# Grabber_DIOT.net
KiCad netlist of a schematic drawn in Altium Designer
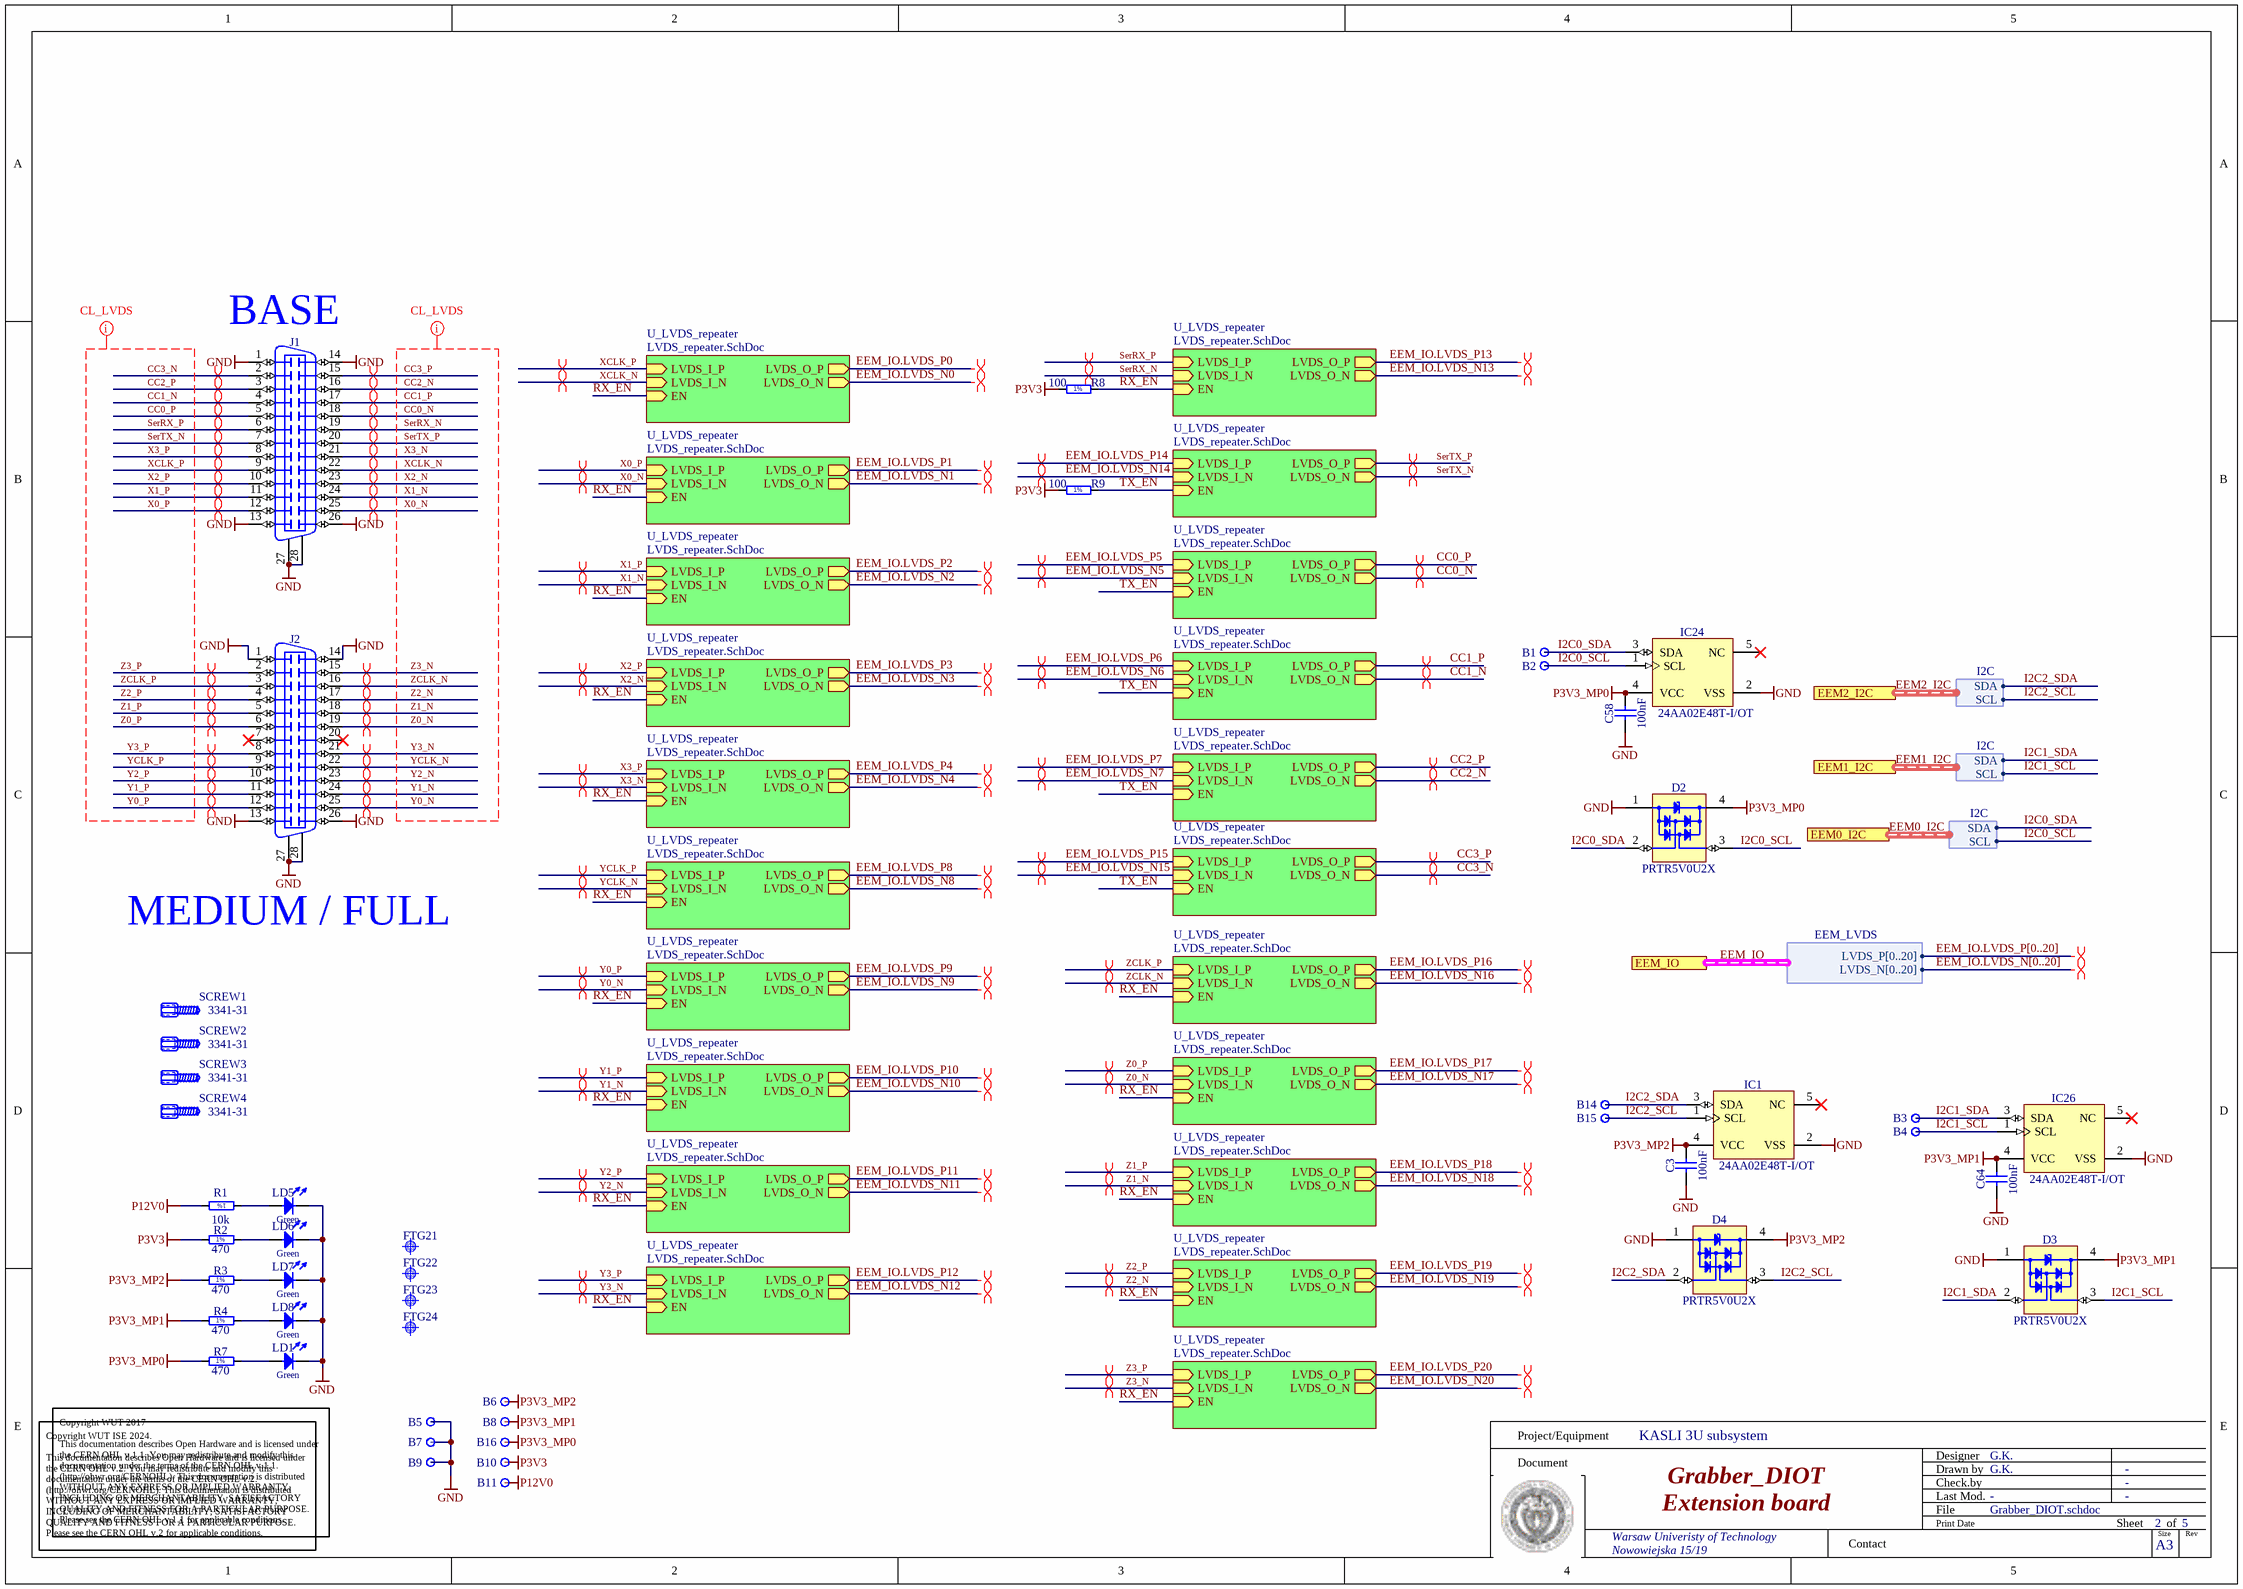
[diagram p0: Grabber_DIOT.schdoc]

(export (version "E")
  (design (tool "Eeschema 10.0.6"))
  (components
    (comp (ref "B1")
      (value "Plated Hole")
      (footprint "c100h50")
      (description "Single Terminal Socket")
      (fields (field (name "PART NUMBER") "PLATED_HOLE0.6_PAD1.3") (field (name "AUTHOR") "CERN DEM MR"))
      (libsource (lib "Eletro-mechanical") (part "Single Terminal Socket"))
    )
    (comp (ref "B2")
      (value "Plated Hole")
      (footprint "c100h50")
      (description "Single Terminal Socket")
      (fields (field (name "PART NUMBER") "PLATED_HOLE0.6_PAD1.3") (field (name "AUTHOR") "CERN DEM MR"))
      (libsource (lib "Eletro-mechanical") (part "Single Terminal Socket"))
    )
    (comp (ref "B3")
      (value "Plated Hole")
      (footprint "c100h50")
      (description "Single Terminal Socket")
      (fields (field (name "PART NUMBER") "PLATED_HOLE0.6_PAD1.3") (field (name "AUTHOR") "CERN DEM MR"))
      (libsource (lib "Eletro-mechanical") (part "Single Terminal Socket"))
    )
    (comp (ref "B4")
      (value "Plated Hole")
      (footprint "c100h50")
      (description "Single Terminal Socket")
      (fields (field (name "PART NUMBER") "PLATED_HOLE0.6_PAD1.3") (field (name "AUTHOR") "CERN DEM MR"))
      (libsource (lib "Eletro-mechanical") (part "Single Terminal Socket"))
    )
    (comp (ref "B5")
      (value "Plated Hole")
      (footprint "c100h50")
      (description "Single Terminal Socket")
      (fields (field (name "PART NUMBER") "PLATED_HOLE0.6_PAD1.3") (field (name "AUTHOR") "CERN DEM MR"))
      (libsource (lib "Eletro-mechanical") (part "Single Terminal Socket"))
    )
    (comp (ref "B6")
      (value "Plated Hole")
      (footprint "c100h50")
      (description "Single Terminal Socket")
      (fields (field (name "PART NUMBER") "PLATED_HOLE0.6_PAD1.3") (field (name "AUTHOR") "CERN DEM MR"))
      (libsource (lib "Eletro-mechanical") (part "Single Terminal Socket"))
    )
    (comp (ref "B7")
      (value "Plated Hole")
      (footprint "c100h50")
      (description "Single Terminal Socket")
      (fields (field (name "PART NUMBER") "PLATED_HOLE0.6_PAD1.3") (field (name "AUTHOR") "CERN DEM MR"))
      (libsource (lib "Eletro-mechanical") (part "Single Terminal Socket"))
    )
    (comp (ref "B8")
      (value "Plated Hole")
      (footprint "c100h50")
      (description "Single Terminal Socket")
      (fields (field (name "PART NUMBER") "PLATED_HOLE0.6_PAD1.3") (field (name "AUTHOR") "CERN DEM MR"))
      (libsource (lib "Eletro-mechanical") (part "Single Terminal Socket"))
    )
    (comp (ref "B9")
      (value "Plated Hole")
      (footprint "c100h50")
      (description "Single Terminal Socket")
      (fields (field (name "PART NUMBER") "PLATED_HOLE0.6_PAD1.3") (field (name "AUTHOR") "CERN DEM MR"))
      (libsource (lib "Eletro-mechanical") (part "Single Terminal Socket"))
    )
    (comp (ref "B10")
      (value "Plated Hole")
      (footprint "c100h50")
      (description "Single Terminal Socket")
      (fields (field (name "PART NUMBER") "PLATED_HOLE0.6_PAD1.3") (field (name "AUTHOR") "CERN DEM MR"))
      (libsource (lib "Eletro-mechanical") (part "Single Terminal Socket"))
    )
    (comp (ref "B11")
      (value "Plated Hole")
      (footprint "c100h50")
      (description "Single Terminal Socket")
      (fields (field (name "PART NUMBER") "PLATED_HOLE0.6_PAD1.3") (field (name "AUTHOR") "CERN DEM MR"))
      (libsource (lib "Eletro-mechanical") (part "Single Terminal Socket"))
    )
    (comp (ref "B14")
      (value "Plated Hole")
      (footprint "c100h50")
      (description "Single Terminal Socket")
      (fields (field (name "PART NUMBER") "PLATED_HOLE0.6_PAD1.3") (field (name "AUTHOR") "CERN DEM MR"))
      (libsource (lib "Eletro-mechanical") (part "Single Terminal Socket"))
    )
    (comp (ref "B15")
      (value "Plated Hole")
      (footprint "c100h50")
      (description "Single Terminal Socket")
      (fields (field (name "PART NUMBER") "PLATED_HOLE0.6_PAD1.3") (field (name "AUTHOR") "CERN DEM MR"))
      (libsource (lib "Eletro-mechanical") (part "Single Terminal Socket"))
    )
    (comp (ref "B16")
      (value "Plated Hole")
      (footprint "c100h50")
      (description "Single Terminal Socket")
      (fields (field (name "PART NUMBER") "PLATED_HOLE0.6_PAD1.3") (field (name "AUTHOR") "CERN DEM MR"))
      (libsource (lib "Eletro-mechanical") (part "Single Terminal Socket"))
    )
    (comp (ref "C3")
      (value "100nF")
      (footprint "CAPC1005X55N")
      (description "Non-polarised capacitor")
      (fields
        (field (name "PART NUMBER") "CC0402_100NF_16V_10%_X5R")
        (field (name "VOLTAGE") "16V")
        (field (name "AUTHOR") "CERN DEM JLC")
      )
      (libsource (lib "Capacitors") (part "Capacitor - non polarized"))
    )
    (comp (ref "C58")
      (value "100nF")
      (footprint "CAPC1005X55N")
      (description "Non-polarised capacitor")
      (fields
        (field (name "PART NUMBER") "CC0402_100NF_16V_10%_X5R")
        (field (name "VOLTAGE") "16V")
        (field (name "AUTHOR") "CERN DEM JLC")
      )
      (libsource (lib "Capacitors") (part "Capacitor - non polarized"))
    )
    (comp (ref "C64")
      (value "100nF")
      (footprint "CAPC1005X55N")
      (description "Non-polarised capacitor")
      (fields
        (field (name "PART NUMBER") "CC0402_100NF_16V_10%_X5R")
        (field (name "VOLTAGE") "16V")
        (field (name "AUTHOR") "CERN DEM JLC")
      )
      (libsource (lib "Capacitors") (part "Capacitor - non polarized"))
    )
    (comp (ref "D2")
      (value "PRTR5V0U2X")
      (footprint "SOT190P230X110-4N")
      (description "Ultra Low Capacitance Double Rail-to-Rail ESD Protection Diode")
      (fields
        (field (name "VOLTAGE") "5.5V")
        (field (name "MANUFACTURER") "NXP SEMICONDUCTORS")
        (field (name "AUTHOR") "CERN DEM JLC")
      )
      (libsource (lib "ICs And Semiconductors") (part "PRTR5V0U2X"))
    )
    (comp (ref "D3")
      (value "PRTR5V0U2X")
      (footprint "SOT190P230X110-4N")
      (description "Ultra Low Capacitance Double Rail-to-Rail ESD Protection Diode")
      (fields
        (field (name "VOLTAGE") "5.5V")
        (field (name "MANUFACTURER") "NXP SEMICONDUCTORS")
        (field (name "AUTHOR") "CERN DEM JLC")
      )
      (libsource (lib "ICs And Semiconductors") (part "PRTR5V0U2X"))
    )
    (comp (ref "D4")
      (value "PRTR5V0U2X")
      (footprint "SOT190P230X110-4N")
      (description "Ultra Low Capacitance Double Rail-to-Rail ESD Protection Diode")
      (fields
        (field (name "VOLTAGE") "5.5V")
        (field (name "MANUFACTURER") "NXP SEMICONDUCTORS")
        (field (name "AUTHOR") "CERN DEM JLC")
      )
      (libsource (lib "ICs And Semiconductors") (part "PRTR5V0U2X"))
    )
    (comp (ref "FTG21")
      (value "Use only in PCB")
      (footprint "FIDUCIAL_TOP_C100-200")
      (description "Fiducial Target")
      (fields (field (name "PART NUMBER") "FIDUCIAL_TARGET_C100-200") (field (name "AUTHOR") "CERN DEM JLC"))
      (libsource (lib "Eletro-mechanical") (part "Fiducial Target"))
    )
    (comp (ref "FTG22")
      (value "Use only in PCB")
      (footprint "FIDUCIAL_TOP_S100-200")
      (description "Fiducial Target")
      (fields (field (name "PART NUMBER") "FIDUCIAL_TARGET_S100-200") (field (name "AUTHOR") "CERN DEM JLC"))
      (libsource (lib "Eletro-mechanical") (part "Fiducial Target"))
    )
    (comp (ref "FTG23")
      (value "Use only in PCB")
      (footprint "FIDUCIAL_TOP_S200-400")
      (description "Fiducial Target")
      (fields (field (name "PART NUMBER") "FIDUCIAL_TARGET_S200-400") (field (name "AUTHOR") "CERN DEM JLC"))
      (libsource (lib "Eletro-mechanical") (part "Fiducial Target"))
    )
    (comp (ref "FTG24")
      (value "Use only in PCB")
      (footprint "FIDUCIAL_TOP_S100-200")
      (description "Fiducial Target")
      (fields (field (name "PART NUMBER") "FIDUCIAL_TARGET_S100-200") (field (name "AUTHOR") "CERN DEM JLC"))
      (libsource (lib "Eletro-mechanical") (part "Fiducial Target"))
    )
    (comp (ref "IC1")
      (value "24AA02E48T-I/OT")
      (footprint "SOT95P280X145-5N")
      (description "1.7V-5.5V, 2K I2C Serial EEPROM With EUI-48 Node Identity")
      (fields (field (name "MANUFACTURER") "MICROCHIP TECHNOLOGY") (field (name "AUTHOR") "CERN DEM MR"))
      (libsource (lib "ICs And Semiconductors") (part "24AA02E48T-I/OT"))
    )
    (comp (ref "IC24")
      (value "24AA02E48T-I/OT")
      (footprint "SOT95P280X145-5N")
      (description "1.7V-5.5V, 2K I2C Serial EEPROM With EUI-48 Node Identity")
      (fields (field (name "MANUFACTURER") "MICROCHIP TECHNOLOGY") (field (name "AUTHOR") "CERN DEM MR"))
      (libsource (lib "ICs And Semiconductors") (part "24AA02E48T-I/OT"))
    )
    (comp (ref "IC26")
      (value "24AA02E48T-I/OT")
      (footprint "SOT95P280X145-5N")
      (description "1.7V-5.5V, 2K I2C Serial EEPROM With EUI-48 Node Identity")
      (fields (field (name "MANUFACTURER") "MICROCHIP TECHNOLOGY") (field (name "AUTHOR") "CERN DEM MR"))
      (libsource (lib "ICs And Semiconductors") (part "24AA02E48T-I/OT"))
    )
    (comp (ref "J1")
      (value "N10226-5212PC")
      (footprint "3M_N10226-5212PC")
      (description "Connector Mini D Ribbon (MDR) 26 Female")
      (fields (field (name "MANUFACTURER") "3M") (field (name "AUTHOR") "CERN DEM JLC"))
      (libsource (lib "Connectors") (part "Connector MDR 26 Female"))
    )
    (comp (ref "J2")
      (value "N10226-5212PC")
      (footprint "3M_N10226-5212PC")
      (description "Connector Mini D Ribbon (MDR) 26 Female")
      (fields (field (name "MANUFACTURER") "3M") (field (name "AUTHOR") "CERN DEM JLC"))
      (libsource (lib "Connectors") (part "Connector MDR 26 Female"))
    )
    (comp (ref "LD1")
      (value "Green")
      (footprint "LED_KINGBRIGHT_KP-1608CGCK")
      (description "LED Green 1C 2A")
      (fields
        (field (name "PART NUMBER") "KPH-1608CGCK")
        (field (name "MANUFACTURER") "KINGBRIGHT")
        (field (name "AUTHOR") "CERN DEM JLC")
      )
      (libsource (lib "ICs And Semiconductors") (part "LED Green 1C 2A"))
    )
    (comp (ref "LD5")
      (value "Green")
      (footprint "LED_KINGBRIGHT_KP-1608CGCK")
      (description "LED Green 1C 2A")
      (fields
        (field (name "PART NUMBER") "KPH-1608CGCK")
        (field (name "MANUFACTURER") "KINGBRIGHT")
        (field (name "AUTHOR") "CERN DEM JLC")
      )
      (libsource (lib "ICs And Semiconductors") (part "LED Green 1C 2A"))
    )
    (comp (ref "LD6")
      (value "Green")
      (footprint "LED_KINGBRIGHT_KP-1608CGCK")
      (description "LED Green 1C 2A")
      (fields
        (field (name "PART NUMBER") "KPH-1608CGCK")
        (field (name "MANUFACTURER") "KINGBRIGHT")
        (field (name "AUTHOR") "CERN DEM JLC")
      )
      (libsource (lib "ICs And Semiconductors") (part "LED Green 1C 2A"))
    )
    (comp (ref "LD7")
      (value "Green")
      (footprint "LED_KINGBRIGHT_KP-1608CGCK")
      (description "LED Green 1C 2A")
      (fields
        (field (name "PART NUMBER") "KPH-1608CGCK")
        (field (name "MANUFACTURER") "KINGBRIGHT")
        (field (name "AUTHOR") "CERN DEM JLC")
      )
      (libsource (lib "ICs And Semiconductors") (part "LED Green 1C 2A"))
    )
    (comp (ref "LD8")
      (value "Green")
      (footprint "LED_KINGBRIGHT_KP-1608CGCK")
      (description "LED Green 1C 2A")
      (fields
        (field (name "PART NUMBER") "KPH-1608CGCK")
        (field (name "MANUFACTURER") "KINGBRIGHT")
        (field (name "AUTHOR") "CERN DEM JLC")
      )
      (libsource (lib "ICs And Semiconductors") (part "LED Green 1C 2A"))
    )
    (comp (ref "R1")
      (value "10k")
      (footprint "RESC1005X40N")
      (description "Resistor - 1%")
      (fields
        (field (name "PART NUMBER") "R0402_10K_1%_0.0625W_100PPM")
        (field (name "POWER") "0.0625W")
        (field (name "AUTHOR") "CERN DEM JLC")
      )
      (libsource (lib "Resistors") (part "Resistor - 1%"))
    )
    (comp (ref "R2")
      (value "470")
      (footprint "RESC1005X40N")
      (description "Resistor - 1%")
      (fields
        (field (name "PART NUMBER") "R0402_470R_1%_0.0625W_100PPM")
        (field (name "POWER") "0.0625W")
        (field (name "AUTHOR") "CERN DEM JLC")
      )
      (libsource (lib "Resistors") (part "Resistor - 1%"))
    )
    (comp (ref "R3")
      (value "470")
      (footprint "RESC1005X40N")
      (description "Resistor - 1%")
      (fields
        (field (name "PART NUMBER") "R0402_470R_1%_0.0625W_100PPM")
        (field (name "POWER") "0.0625W")
        (field (name "AUTHOR") "CERN DEM JLC")
      )
      (libsource (lib "Resistors") (part "Resistor - 1%"))
    )
    (comp (ref "R4")
      (value "470")
      (footprint "RESC1005X40N")
      (description "Resistor - 1%")
      (fields
        (field (name "PART NUMBER") "R0402_470R_1%_0.0625W_100PPM")
        (field (name "POWER") "0.0625W")
        (field (name "AUTHOR") "CERN DEM JLC")
      )
      (libsource (lib "Resistors") (part "Resistor - 1%"))
    )
    (comp (ref "R7")
      (value "470")
      (footprint "RESC1005X40N")
      (description "Resistor - 1%")
      (fields
        (field (name "PART NUMBER") "R0402_470R_1%_0.0625W_100PPM")
        (field (name "POWER") "0.0625W")
        (field (name "AUTHOR") "CERN DEM JLC")
      )
      (libsource (lib "Resistors") (part "Resistor - 1%"))
    )
    (comp (ref "R8")
      (value "100")
      (footprint "RESC1005X40N")
      (description "Resistor - 1%")
      (fields
        (field (name "PART NUMBER") "R0402_100R_1%_0.1W_100PPM")
        (field (name "POWER") "0.1W")
        (field (name "AUTHOR") "CERN DEM JLC")
      )
      (libsource (lib "Resistors") (part "Resistor - 1%"))
    )
    (comp (ref "R9")
      (value "100")
      (footprint "RESC1005X40N")
      (description "Resistor - 1%")
      (fields
        (field (name "PART NUMBER") "R0402_100R_1%_0.1W_100PPM")
        (field (name "POWER") "0.1W")
        (field (name "AUTHOR") "CERN DEM JLC")
      )
      (libsource (lib "Resistors") (part "Resistor - 1%"))
    )
    (comp (ref "SCREW1")
      (value "3341-31")
      (footprint "3M_3341-31")
      (description "VHDCI Female Screw Lock")
      (fields (field (name "MANUFACTURER") "3M") (field (name "AUTHOR") "GK"))
      (libsource (lib "LIBRARY_SCH") (part "MECH_MDR_screw_lock"))
    )
    (comp (ref "SCREW2")
      (value "3341-31")
      (footprint "3M_3341-31")
      (description "VHDCI Female Screw Lock")
      (fields (field (name "MANUFACTURER") "3M") (field (name "AUTHOR") "GK"))
      (libsource (lib "LIBRARY_SCH") (part "MECH_MDR_screw_lock"))
    )
    (comp (ref "SCREW3")
      (value "3341-31")
      (footprint "3M_3341-31")
      (description "VHDCI Female Screw Lock")
      (fields (field (name "MANUFACTURER") "3M") (field (name "AUTHOR") "GK"))
      (libsource (lib "LIBRARY_SCH") (part "MECH_MDR_screw_lock"))
    )
    (comp (ref "SCREW4")
      (value "3341-31")
      (footprint "3M_3341-31")
      (description "VHDCI Female Screw Lock")
      (fields (field (name "MANUFACTURER") "3M") (field (name "AUTHOR") "GK"))
      (libsource (lib "LIBRARY_SCH") (part "MECH_MDR_screw_lock"))
    )
  )
  (nets
    (net (code "5") (name "/CC0_N") (class "Default")
      (node (ref "J1") (pin "18") (pinfunction "18_18") (pintype "bidirectional"))
    )
    (net (code "6") (name "/CC0_P") (class "Default")
      (node (ref "J1") (pin "5") (pinfunction "5_5") (pintype "bidirectional"))
    )
    (net (code "7") (name "/CC1_N") (class "Default")
      (node (ref "J1") (pin "4") (pinfunction "4_4") (pintype "bidirectional"))
    )
    (net (code "8") (name "/CC1_P") (class "Default")
      (node (ref "J1") (pin "17") (pinfunction "17_17") (pintype "bidirectional"))
    )
    (net (code "9") (name "/CC2_N") (class "Default")
      (node (ref "J1") (pin "16") (pinfunction "16_16") (pintype "bidirectional"))
    )
    (net (code "10") (name "/CC2_P") (class "Default")
      (node (ref "J1") (pin "3") (pinfunction "3_3") (pintype "bidirectional"))
    )
    (net (code "11") (name "/CC3_N") (class "Default")
      (node (ref "J1") (pin "2") (pinfunction "2_2") (pintype "bidirectional"))
    )
    (net (code "12") (name "/CC3_P") (class "Default")
      (node (ref "J1") (pin "15") (pinfunction "15_15") (pintype "bidirectional"))
    )
    (net (code "59") (name "/I2C0_SCL") (class "Default")
      (node (ref "B2") (pin "1") (pinfunction "1_1") (pintype "bidirectional"))
      (node (ref "D2") (pin "3") (pinfunction "I/O2_3") (pintype "bidirectional"))
      (node (ref "IC24") (pin "1") (pinfunction "SCL_1") (pintype "input"))
    )
    (net (code "60") (name "/I2C0_SDA") (class "Default")
      (node (ref "B1") (pin "1") (pinfunction "1_1") (pintype "bidirectional"))
      (node (ref "D2") (pin "2") (pinfunction "I/O1_2") (pintype "bidirectional"))
      (node (ref "IC24") (pin "3") (pinfunction "SDA_3") (pintype "bidirectional"))
    )
    (net (code "61") (name "/I2C1_SCL") (class "Default")
      (node (ref "B4") (pin "1") (pinfunction "1_1") (pintype "bidirectional"))
      (node (ref "D3") (pin "3") (pinfunction "I/O2_3") (pintype "bidirectional"))
      (node (ref "IC26") (pin "1") (pinfunction "SCL_1") (pintype "input"))
    )
    (net (code "62") (name "/I2C1_SDA") (class "Default")
      (node (ref "B3") (pin "1") (pinfunction "1_1") (pintype "bidirectional"))
      (node (ref "D3") (pin "2") (pinfunction "I/O1_2") (pintype "bidirectional"))
      (node (ref "IC26") (pin "3") (pinfunction "SDA_3") (pintype "bidirectional"))
    )
    (net (code "63") (name "/I2C2_SCL") (class "Default")
      (node (ref "B15") (pin "1") (pinfunction "1_1") (pintype "bidirectional"))
      (node (ref "D4") (pin "3") (pinfunction "I/O2_3") (pintype "bidirectional"))
      (node (ref "IC1") (pin "1") (pinfunction "SCL_1") (pintype "input"))
    )
    (net (code "64") (name "/I2C2_SDA") (class "Default")
      (node (ref "B14") (pin "1") (pinfunction "1_1") (pintype "bidirectional"))
      (node (ref "D4") (pin "2") (pinfunction "I/O1_2") (pintype "bidirectional"))
      (node (ref "IC1") (pin "3") (pinfunction "SDA_3") (pintype "bidirectional"))
    )
    (net (code "65") (name "/RX_EN") (class "Default")
      (node (ref "R8") (pin "2") (pinfunction "2_2") (pintype "passive"))
    )
    (net (code "66") (name "/SerRX_N") (class "Default")
      (node (ref "J1") (pin "19") (pinfunction "19_19") (pintype "bidirectional"))
    )
    (net (code "67") (name "/SerRX_P") (class "Default")
      (node (ref "J1") (pin "6") (pinfunction "6_6") (pintype "bidirectional"))
    )
    (net (code "68") (name "/SerTX_N") (class "Default")
      (node (ref "J1") (pin "7") (pinfunction "7_7") (pintype "bidirectional"))
    )
    (net (code "69") (name "/SerTX_P") (class "Default")
      (node (ref "J1") (pin "20") (pinfunction "20_20") (pintype "bidirectional"))
    )
    (net (code "70") (name "/TX_EN") (class "Default")
      (node (ref "R9") (pin "2") (pinfunction "2_2") (pintype "passive"))
    )
    (net (code "71") (name "/X0_N") (class "Default")
      (node (ref "J1") (pin "25") (pinfunction "25_25") (pintype "bidirectional"))
    )
    (net (code "72") (name "/X0_P") (class "Default")
      (node (ref "J1") (pin "12") (pinfunction "12_12") (pintype "bidirectional"))
    )
    (net (code "73") (name "/X1_N") (class "Default")
      (node (ref "J1") (pin "24") (pinfunction "24_24") (pintype "bidirectional"))
    )
    (net (code "74") (name "/X1_P") (class "Default")
      (node (ref "J1") (pin "11") (pinfunction "11_11") (pintype "bidirectional"))
    )
    (net (code "75") (name "/X2_N") (class "Default")
      (node (ref "J1") (pin "23") (pinfunction "23_23") (pintype "bidirectional"))
    )
    (net (code "76") (name "/X2_P") (class "Default")
      (node (ref "J1") (pin "10") (pinfunction "10_10") (pintype "bidirectional"))
    )
    (net (code "77") (name "/X3_N") (class "Default")
      (node (ref "J1") (pin "21") (pinfunction "21_21") (pintype "bidirectional"))
    )
    (net (code "78") (name "/X3_P") (class "Default")
      (node (ref "J1") (pin "8") (pinfunction "8_8") (pintype "bidirectional"))
    )
    (net (code "79") (name "/XCLK_N") (class "Default")
      (node (ref "J1") (pin "22") (pinfunction "22_22") (pintype "bidirectional"))
    )
    (net (code "80") (name "/XCLK_P") (class "Default")
      (node (ref "J1") (pin "9") (pinfunction "9_9") (pintype "bidirectional"))
    )
    (net (code "81") (name "/Y0_N") (class "Default")
      (node (ref "J2") (pin "25") (pinfunction "25_25") (pintype "bidirectional"))
    )
    (net (code "82") (name "/Y0_P") (class "Default")
      (node (ref "J2") (pin "12") (pinfunction "12_12") (pintype "bidirectional"))
    )
    (net (code "83") (name "/Y1_N") (class "Default")
      (node (ref "J2") (pin "24") (pinfunction "24_24") (pintype "bidirectional"))
    )
    (net (code "84") (name "/Y1_P") (class "Default")
      (node (ref "J2") (pin "11") (pinfunction "11_11") (pintype "bidirectional"))
    )
    (net (code "85") (name "/Y2_N") (class "Default")
      (node (ref "J2") (pin "23") (pinfunction "23_23") (pintype "bidirectional"))
    )
    (net (code "86") (name "/Y2_P") (class "Default")
      (node (ref "J2") (pin "10") (pinfunction "10_10") (pintype "bidirectional"))
    )
    (net (code "87") (name "/Y3_N") (class "Default")
      (node (ref "J2") (pin "21") (pinfunction "21_21") (pintype "bidirectional"))
    )
    (net (code "88") (name "/Y3_P") (class "Default")
      (node (ref "J2") (pin "8") (pinfunction "8_8") (pintype "bidirectional"))
    )
    (net (code "89") (name "/YCLK_N") (class "Default")
      (node (ref "J2") (pin "22") (pinfunction "22_22") (pintype "bidirectional"))
    )
    (net (code "90") (name "/YCLK_P") (class "Default")
      (node (ref "J2") (pin "9") (pinfunction "9_9") (pintype "bidirectional"))
    )
    (net (code "91") (name "/Z0_N") (class "Default")
      (node (ref "J2") (pin "19") (pinfunction "19_19") (pintype "bidirectional"))
    )
    (net (code "92") (name "/Z0_P") (class "Default")
      (node (ref "J2") (pin "6") (pinfunction "6_6") (pintype "bidirectional"))
    )
    (net (code "93") (name "/Z1_N") (class "Default")
      (node (ref "J2") (pin "18") (pinfunction "18_18") (pintype "bidirectional"))
    )
    (net (code "94") (name "/Z1_P") (class "Default")
      (node (ref "J2") (pin "5") (pinfunction "5_5") (pintype "bidirectional"))
    )
    (net (code "95") (name "/Z2_N") (class "Default")
      (node (ref "J2") (pin "17") (pinfunction "17_17") (pintype "bidirectional"))
    )
    (net (code "96") (name "/Z2_P") (class "Default")
      (node (ref "J2") (pin "4") (pinfunction "4_4") (pintype "bidirectional"))
    )
    (net (code "97") (name "/Z3_N") (class "Default")
      (node (ref "J2") (pin "15") (pinfunction "15_15") (pintype "bidirectional"))
    )
    (net (code "98") (name "/Z3_P") (class "Default")
      (node (ref "J2") (pin "2") (pinfunction "2_2") (pintype "bidirectional"))
    )
    (net (code "99") (name "/ZCLK_N") (class "Default")
      (node (ref "J2") (pin "16") (pinfunction "16_16") (pintype "bidirectional"))
    )
    (net (code "100") (name "/ZCLK_P") (class "Default")
      (node (ref "J2") (pin "3") (pinfunction "3_3") (pintype "bidirectional"))
    )
    (net (code "102") (name "GND") (class "Default")
      (node (ref "B5") (pin "1") (pinfunction "1_1") (pintype "bidirectional"))
      (node (ref "B7") (pin "1") (pinfunction "1_1") (pintype "bidirectional"))
      (node (ref "B9") (pin "1") (pinfunction "1_1") (pintype "bidirectional"))
      (node (ref "C3") (pin "1") (pinfunction "1_1") (pintype "passive"))
      (node (ref "C58") (pin "1") (pinfunction "1_1") (pintype "passive"))
      (node (ref "C64") (pin "1") (pinfunction "1_1") (pintype "passive"))
      (node (ref "D2") (pin "1") (pinfunction "GND_1") (pintype "power_in"))
      (node (ref "D3") (pin "1") (pinfunction "GND_1") (pintype "power_in"))
      (node (ref "D4") (pin "1") (pinfunction "GND_1") (pintype "power_in"))
      (node (ref "IC1") (pin "2") (pinfunction "VSS_2") (pintype "power_in"))
      (node (ref "IC24") (pin "2") (pinfunction "VSS_2") (pintype "power_in"))
      (node (ref "IC26") (pin "2") (pinfunction "VSS_2") (pintype "power_in"))
      (node (ref "J1") (pin "1") (pinfunction "1_1") (pintype "bidirectional"))
      (node (ref "J1") (pin "13") (pinfunction "13_13") (pintype "bidirectional"))
      (node (ref "J1") (pin "14") (pinfunction "14_14") (pintype "bidirectional"))
      (node (ref "J1") (pin "26") (pinfunction "26_26") (pintype "bidirectional"))
      (node (ref "J1") (pin "27") (pinfunction "27_27") (pintype "passive"))
      (node (ref "J1") (pin "28") (pinfunction "28_28") (pintype "passive"))
      (node (ref "J2") (pin "1") (pinfunction "1_1") (pintype "bidirectional"))
      (node (ref "J2") (pin "13") (pinfunction "13_13") (pintype "bidirectional"))
      (node (ref "J2") (pin "14") (pinfunction "14_14") (pintype "bidirectional"))
      (node (ref "J2") (pin "26") (pinfunction "26_26") (pintype "bidirectional"))
      (node (ref "J2") (pin "27") (pinfunction "27_27") (pintype "passive"))
      (node (ref "J2") (pin "28") (pinfunction "28_28") (pintype "passive"))
      (node (ref "LD1") (pin "1") (pinfunction "C_1") (pintype "passive"))
      (node (ref "LD5") (pin "1") (pinfunction "C_1") (pintype "passive"))
      (node (ref "LD6") (pin "1") (pinfunction "C_1") (pintype "passive"))
      (node (ref "LD7") (pin "1") (pinfunction "C_1") (pintype "passive"))
      (node (ref "LD8") (pin "1") (pinfunction "C_1") (pintype "passive"))
    )
    (net (code "103") (name "Net-(LD1-A)") (class "Default")
      (node (ref "LD1") (pin "2") (pinfunction "A_2") (pintype "passive"))
      (node (ref "R7") (pin "2") (pinfunction "2_2") (pintype "passive"))
    )
    (net (code "104") (name "Net-(LD5-A)") (class "Default")
      (node (ref "LD5") (pin "2") (pinfunction "A_2") (pintype "passive"))
      (node (ref "R1") (pin "1") (pinfunction "1_1") (pintype "passive"))
    )
    (net (code "105") (name "Net-(LD6-A)") (class "Default")
      (node (ref "LD6") (pin "2") (pinfunction "A_2") (pintype "passive"))
      (node (ref "R2") (pin "2") (pinfunction "2_2") (pintype "passive"))
    )
    (net (code "106") (name "Net-(LD7-A)") (class "Default")
      (node (ref "LD7") (pin "2") (pinfunction "A_2") (pintype "passive"))
      (node (ref "R3") (pin "2") (pinfunction "2_2") (pintype "passive"))
    )
    (net (code "107") (name "Net-(LD8-A)") (class "Default")
      (node (ref "LD8") (pin "2") (pinfunction "A_2") (pintype "passive"))
      (node (ref "R4") (pin "2") (pinfunction "2_2") (pintype "passive"))
    )
    (net (code "108") (name "P3V3") (class "Default")
      (node (ref "B10") (pin "1") (pinfunction "1_1") (pintype "bidirectional"))
      (node (ref "R2") (pin "1") (pinfunction "1_1") (pintype "passive"))
      (node (ref "R8") (pin "1") (pinfunction "1_1") (pintype "passive"))
      (node (ref "R9") (pin "1") (pinfunction "1_1") (pintype "passive"))
    )
    (net (code "109") (name "P3V3_MP0") (class "Default")
      (node (ref "B16") (pin "1") (pinfunction "1_1") (pintype "bidirectional"))
      (node (ref "C58") (pin "2") (pinfunction "2_2") (pintype "passive"))
      (node (ref "D2") (pin "4") (pinfunction "VCC_4") (pintype "power_in"))
      (node (ref "IC24") (pin "4") (pinfunction "VCC_4") (pintype "power_in"))
      (node (ref "R7") (pin "1") (pinfunction "1_1") (pintype "passive"))
    )
    (net (code "110") (name "P3V3_MP1") (class "Default")
      (node (ref "B8") (pin "1") (pinfunction "1_1") (pintype "bidirectional"))
      (node (ref "C64") (pin "2") (pinfunction "2_2") (pintype "passive"))
      (node (ref "D3") (pin "4") (pinfunction "VCC_4") (pintype "power_in"))
      (node (ref "IC26") (pin "4") (pinfunction "VCC_4") (pintype "power_in"))
      (node (ref "R4") (pin "1") (pinfunction "1_1") (pintype "passive"))
    )
    (net (code "111") (name "P3V3_MP2") (class "Default")
      (node (ref "B6") (pin "1") (pinfunction "1_1") (pintype "bidirectional"))
      (node (ref "C3") (pin "2") (pinfunction "2_2") (pintype "passive"))
      (node (ref "D4") (pin "4") (pinfunction "VCC_4") (pintype "power_in"))
      (node (ref "IC1") (pin "4") (pinfunction "VCC_4") (pintype "power_in"))
      (node (ref "R3") (pin "1") (pinfunction "1_1") (pintype "passive"))
    )
    (net (code "112") (name "P12V0") (class "Default")
      (node (ref "B11") (pin "1") (pinfunction "1_1") (pintype "bidirectional"))
      (node (ref "R1") (pin "2") (pinfunction "2_2") (pintype "passive"))
    )
    (net (code "113") (name "unconnected-(IC1-NC-Pad5)") (class "Default")
      (node (ref "IC1") (pin "5") (pinfunction "NC_5") (pintype "passive+no_connect"))
    )
    (net (code "114") (name "unconnected-(IC24-NC-Pad5)") (class "Default")
      (node (ref "IC24") (pin "5") (pinfunction "NC_5") (pintype "passive+no_connect"))
    )
    (net (code "115") (name "unconnected-(IC26-NC-Pad5)") (class "Default")
      (node (ref "IC26") (pin "5") (pinfunction "NC_5") (pintype "passive+no_connect"))
    )
    (net (code "116") (name "unconnected-(J2-Pad7)") (class "Default")
      (node (ref "J2") (pin "7") (pinfunction "7_7") (pintype "bidirectional+no_connect"))
    )
    (net (code "117") (name "unconnected-(J2-Pad20)") (class "Default")
      (node (ref "J2") (pin "20") (pinfunction "20_20") (pintype "bidirectional+no_connect"))
    )
  )
)
